# 2025-03-07_main_board.net
KiCad netlist of a schematic drawn in EAGLE
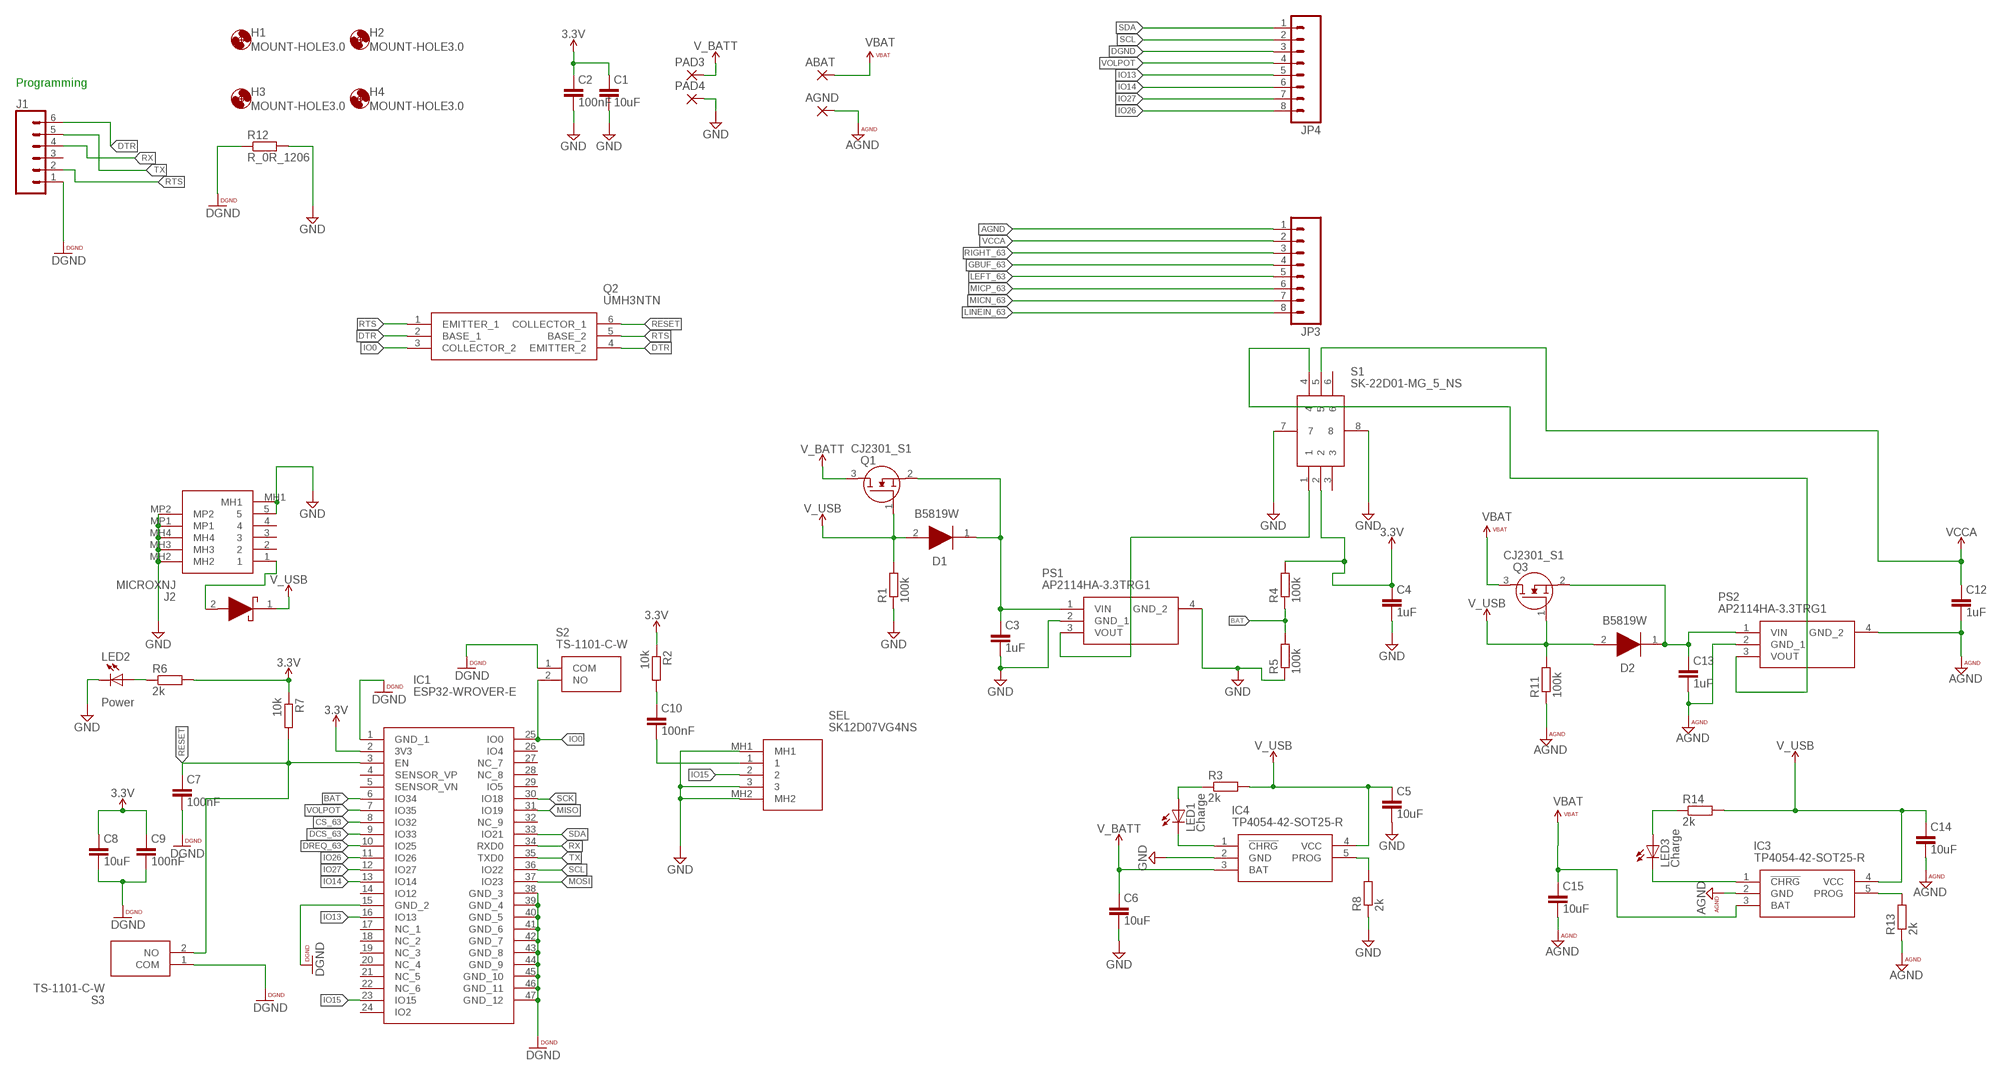
[diagram p0: schematic, sheet 1, part 1 of 2]
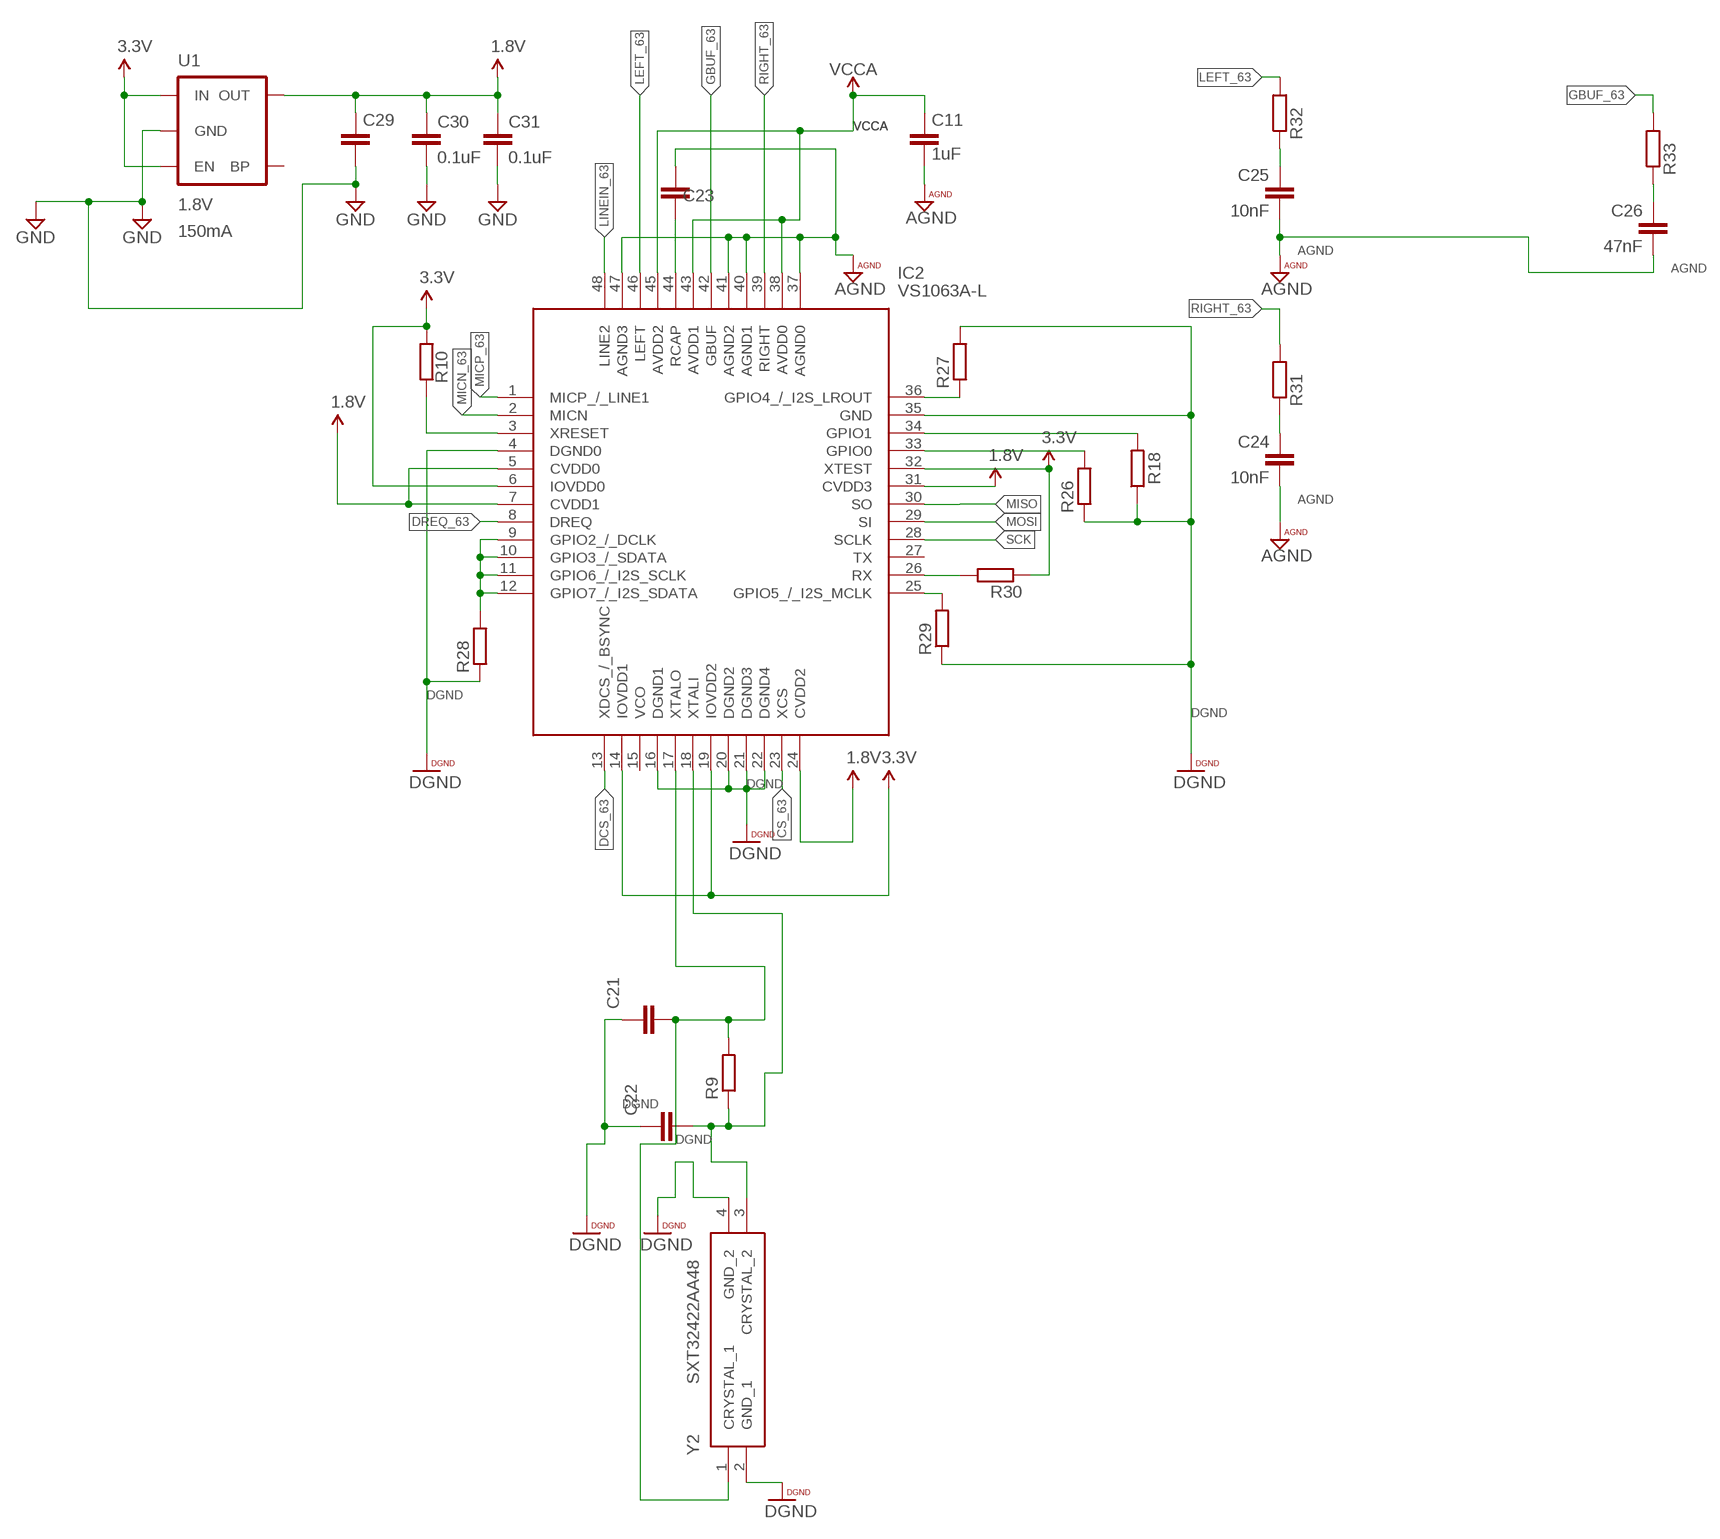
[diagram p1: schematic, sheet 1, part 2 of 2]

(export (version "E")
  (design (tool "Eeschema 10.0.6"))
  (components
    (comp (ref "ABAT")
      (value "2,54/0,8")
      (footprint "eagle-import:2,54_0,8")
      (libsource (lib "eagle-import") (part "2,54/0,8"))
    )
    (comp (ref "AGND")
      (value "2,54/0,8")
      (footprint "eagle-import:2,54_0,8")
      (libsource (lib "eagle-import") (part "2,54/0,8"))
    )
    (comp (ref "C1")
      (value "10uF")
      (footprint "eagle-import:C0603")
      (fields (field (name "LCSC_PART") "C96446"))
      (libsource (lib "eagle-import") (part "C__060310UF/25V"))
    )
    (comp (ref "C2")
      (value "100nF")
      (footprint "eagle-import:C0603")
      (fields (field (name "LCSC_PART") "C14663"))
      (libsource (lib "eagle-import") (part "C__0603100NF/50V"))
    )
    (comp (ref "C3")
      (value "1uF")
      (footprint "eagle-import:C0402")
      (fields (field (name "LCSC_PART") "C52923"))
      (libsource (lib "eagle-import") (part "C__04021UF/25V"))
    )
    (comp (ref "C4")
      (value "1uF")
      (footprint "eagle-import:C0402")
      (fields (field (name "LCSC_PART") "C52923"))
      (libsource (lib "eagle-import") (part "C__04021UF/25V"))
    )
    (comp (ref "C5")
      (value "10uF")
      (footprint "eagle-import:C0603")
      (fields (field (name "LCSC_PART") "C96446"))
      (libsource (lib "eagle-import") (part "C__060310UF/25V"))
    )
    (comp (ref "C6")
      (value "10uF")
      (footprint "eagle-import:C0603")
      (fields (field (name "LCSC_PART") "C96446"))
      (libsource (lib "eagle-import") (part "C__060310UF/25V"))
    )
    (comp (ref "C7")
      (value "100nF")
      (footprint "eagle-import:C0603")
      (fields (field (name "LCSC_PART") "C14663"))
      (libsource (lib "eagle-import") (part "C__0603100NF/50V"))
    )
    (comp (ref "C8")
      (value "10uF")
      (footprint "eagle-import:C0603")
      (fields (field (name "LCSC_PART") "C96446"))
      (libsource (lib "eagle-import") (part "C__060310UF/25V"))
    )
    (comp (ref "C9")
      (value "100nF")
      (footprint "eagle-import:C0603")
      (fields (field (name "LCSC_PART") "C14663"))
      (libsource (lib "eagle-import") (part "C__0603100NF/50V"))
    )
    (comp (ref "C10")
      (value "100nF")
      (footprint "eagle-import:C0603")
      (fields (field (name "LCSC_PART") "C14663"))
      (libsource (lib "eagle-import") (part "C__0603100NF/50V"))
    )
    (comp (ref "C11")
      (value "1uF")
      (footprint "eagle-import:C0402")
      (fields (field (name "LCSC_PART") "C52923"))
      (libsource (lib "eagle-import") (part "C__04021UF/25V"))
    )
    (comp (ref "C12")
      (value "1uF")
      (footprint "eagle-import:C0402")
      (fields (field (name "LCSC_PART") "C52923"))
      (libsource (lib "eagle-import") (part "C__04021UF/25V"))
    )
    (comp (ref "C13")
      (value "1uF")
      (footprint "eagle-import:C0402")
      (fields (field (name "LCSC_PART") "C52923"))
      (libsource (lib "eagle-import") (part "C__04021UF/25V"))
    )
    (comp (ref "C14")
      (value "10uF")
      (footprint "eagle-import:C0603")
      (fields (field (name "LCSC_PART") "C96446"))
      (libsource (lib "eagle-import") (part "C__060310UF/25V"))
    )
    (comp (ref "C15")
      (value "10uF")
      (footprint "eagle-import:C0603")
      (fields (field (name "LCSC_PART") "C96446"))
      (libsource (lib "eagle-import") (part "C__060310UF/25V"))
    )
    (comp (ref "C21")
      (value "22pF")
      (footprint "eagle-import:C0603")
      (fields (field (name "LCSC_PART") "C38523"))
      (libsource (lib "eagle-import") (part "C__060312PF/50V"))
    )
    (comp (ref "C22")
      (value "22pF")
      (footprint "eagle-import:C0603")
      (fields (field (name "LCSC_PART") "C38523"))
      (libsource (lib "eagle-import") (part "C__060312PF/50V"))
    )
    (comp (ref "C23")
      (value "1.0uF")
      (footprint "eagle-import:C0402")
      (fields (field (name "LCSC_PART") "C52923"))
      (libsource (lib "eagle-import") (part "C__04021UF/25V"))
    )
    (comp (ref "C24")
      (value "10nF")
      (footprint "eagle-import:0603-CAP")
      (libsource (lib "eagle-import") (part "10NF/10000PF-50V-10%(0603)"))
    )
    (comp (ref "C25")
      (value "10nF")
      (footprint "eagle-import:0603-CAP")
      (libsource (lib "eagle-import") (part "10NF/10000PF-50V-10%(0603)"))
    )
    (comp (ref "C26")
      (value "47nF")
      (footprint "eagle-import:0603-CAP")
      (libsource (lib "eagle-import") (part "47NF(0.047UF/47000PF)-25V-5%(0603)SMD"))
    )
    (comp (ref "C29")
      (value "10uF")
      (footprint "eagle-import:C0603")
      (fields (field (name "LCSC_PART") "C96446"))
      (libsource (lib "eagle-import") (part "C__060310UF/25V"))
    )
    (comp (ref "C30")
      (value "0.1uF")
      (footprint "eagle-import:0603-CAP")
      (libsource (lib "eagle-import") (part "0.1UF-25V(+80/-20%)(0603)"))
    )
    (comp (ref "C31")
      (value "0.1uF")
      (footprint "eagle-import:0603-CAP")
      (libsource (lib "eagle-import") (part "0.1UF-25V(+80/-20%)(0603)"))
    )
    (comp (ref "D1")
      (value "B5819W")
      (footprint "eagle-import:SOD3716X125N")
      (libsource (lib "eagle-import") (part "B5819W"))
    )
    (comp (ref "D2")
      (value "B5819W")
      (footprint "eagle-import:SOD3716X125N")
      (libsource (lib "eagle-import") (part "B5819W"))
    )
    (comp (ref "D5")
      (value "BAT760-7")
      (footprint "eagle-import:SOD2513X120N")
      (fields (field (name "MOUSER_PART_NUMBER") "621-BAT760-7"))
      (libsource (lib "eagle-import") (part "BAT760-7"))
    )
    (comp (ref "H1")
      (value "MOUNT-HOLE3.0")
      (footprint "eagle-import:3,0")
      (libsource (lib "eagle-import") (part "MOUNT-HOLE3.0"))
    )
    (comp (ref "H2")
      (value "MOUNT-HOLE3.0")
      (footprint "eagle-import:3,0")
      (libsource (lib "eagle-import") (part "MOUNT-HOLE3.0"))
    )
    (comp (ref "H3")
      (value "MOUNT-HOLE3.0")
      (footprint "eagle-import:3,0")
      (libsource (lib "eagle-import") (part "MOUNT-HOLE3.0"))
    )
    (comp (ref "H4")
      (value "MOUNT-HOLE3.0")
      (footprint "eagle-import:3,0")
      (libsource (lib "eagle-import") (part "MOUNT-HOLE3.0"))
    )
    (comp (ref "IC1")
      (value "ESP32-WROVER-E")
      (footprint "eagle-import:ESP32WROVERE")
      (libsource (lib "eagle-import") (part "ESP32-WROVER-E"))
    )
    (comp (ref "IC2")
      (value "VS1063A-L")
      (footprint "eagle-import:QFP50P900X900X160-48N")
      (libsource (lib "eagle-import") (part "VS1063A-L"))
    )
    (comp (ref "IC3")
      (value "TP4054-42-SOT25-R")
      (footprint "eagle-import:SOT95P280X100-5N")
      (libsource (lib "eagle-import") (part "TP4054-42-SOT25-R"))
    )
    (comp (ref "IC4")
      (value "TP4054-42-SOT25-R")
      (footprint "eagle-import:SOT95P280X100-5N")
      (libsource (lib "eagle-import") (part "TP4054-42-SOT25-R"))
    )
    (comp (ref "J1")
      (value "CONN_06NO_SILK_FEMALE_PTH")
      (footprint "eagle-import:1X06_NO_SILK")
      (libsource (lib "eagle-import") (part "CONN_06NO_SILK_FEMALE_PTH"))
    )
    (comp (ref "J2")
      (value "MICROXNJ")
      (footprint "eagle-import:MICROXNJ")
      (libsource (lib "eagle-import") (part "MICROXNJ"))
    )
    (comp (ref "JP3")
      (value "M08")
      (footprint "eagle-import:1X08_ROUND")
      (libsource (lib "eagle-import") (part "M08"))
    )
    (comp (ref "JP4")
      (value "M08")
      (footprint "eagle-import:1X08_ROUND")
      (libsource (lib "eagle-import") (part "M08"))
    )
    (comp (ref "LED1")
      (value "Charge")
      (footprint "eagle-import:CHIP-LED0603")
      (libsource (lib "eagle-import") (part "LEDCHIP-LED0603"))
    )
    (comp (ref "LED2")
      (value "Power")
      (footprint "eagle-import:CHIP-LED0603")
      (libsource (lib "eagle-import") (part "LEDCHIP-LED0603"))
    )
    (comp (ref "LED3")
      (value "Charge")
      (footprint "eagle-import:CHIP-LED0603")
      (libsource (lib "eagle-import") (part "LEDCHIP-LED0603"))
    )
    (comp (ref "PAD3")
      (value "2,54/0,8")
      (footprint "eagle-import:2,54_0,8")
      (libsource (lib "eagle-import") (part "2,54/0,8"))
    )
    (comp (ref "PAD4")
      (value "2,54/0,8")
      (footprint "eagle-import:2,54_0,8")
      (libsource (lib "eagle-import") (part "2,54/0,8"))
    )
    (comp (ref "PS1")
      (value "AP2114HA-3.3TRG1")
      (footprint "eagle-import:SOT230P700X180-4N")
      (fields (field (name "MOUSER_PART_NUMBER") "621-AP2114HA-3.3TRG1"))
      (libsource (lib "eagle-import") (part "AP2114HA-3.3TRG1"))
    )
    (comp (ref "PS2")
      (value "AP2114HA-3.3TRG1")
      (footprint "eagle-import:SOT230P700X180-4N")
      (fields (field (name "MOUSER_PART_NUMBER") "621-AP2114HA-3.3TRG1"))
      (libsource (lib "eagle-import") (part "AP2114HA-3.3TRG1"))
    )
    (comp (ref "Q1")
      (value "CJ2301_S1")
      (footprint "eagle-import:SOT95P240X115-3N")
      (fields (field (name "MANUFACTURER_PART_NUMBER") "CJ2301 S1"))
      (libsource (lib "eagle-import") (part "CJ2301_S1"))
    )
    (comp (ref "Q2")
      (value "UMH3NTN")
      (footprint "eagle-import:UMH3NTN")
      (fields (field (name "MOUSER_PART_NUMBER") "755-UMH3NTN"))
      (libsource (lib "eagle-import") (part "UMH3NTN"))
    )
    (comp (ref "Q3")
      (value "CJ2301_S1")
      (footprint "eagle-import:SOT95P240X115-3N")
      (fields (field (name "MANUFACTURER_PART_NUMBER") "CJ2301 S1"))
      (libsource (lib "eagle-import") (part "CJ2301_S1"))
    )
    (comp (ref "R1")
      (value "100k")
      (footprint "eagle-import:R0603")
      (fields (field (name "LCSC_PART") "C25803"))
      (libsource (lib "eagle-import") (part "R__0603100K"))
    )
    (comp (ref "R2")
      (value "10k")
      (footprint "eagle-import:R0603")
      (fields (field (name "LCSC_PART") "C25804"))
      (libsource (lib "eagle-import") (part "R__060310K"))
    )
    (comp (ref "R3")
      (value "2k")
      (footprint "eagle-import:R0603")
      (fields (field (name "LCSC_PART") "C22975"))
      (libsource (lib "eagle-import") (part "R__06032K"))
    )
    (comp (ref "R4")
      (value "100k")
      (footprint "eagle-import:R0603")
      (fields (field (name "LCSC_PART") "C25803"))
      (libsource (lib "eagle-import") (part "R__0603100K"))
    )
    (comp (ref "R5")
      (value "100k")
      (footprint "eagle-import:R0603")
      (fields (field (name "LCSC_PART") "C25803"))
      (libsource (lib "eagle-import") (part "R__0603100K"))
    )
    (comp (ref "R6")
      (value "2k")
      (footprint "eagle-import:R0603")
      (fields (field (name "LCSC_PART") "C22975"))
      (libsource (lib "eagle-import") (part "R__06032K"))
    )
    (comp (ref "R7")
      (value "10k")
      (footprint "eagle-import:R0603")
      (fields (field (name "LCSC_PART") "C25804"))
      (libsource (lib "eagle-import") (part "R__060310K"))
    )
    (comp (ref "R8")
      (value "2k")
      (footprint "eagle-import:R0603")
      (fields (field (name "LCSC_PART") "C22975"))
      (libsource (lib "eagle-import") (part "R__06032K"))
    )
    (comp (ref "R9")
      (value "1M")
      (footprint "eagle-import:R0603")
      (fields (field (name "LCSC_PART") "C22935"))
      (libsource (lib "eagle-import") (part "R__06031M"))
    )
    (comp (ref "R10")
      (value "100k")
      (footprint "eagle-import:R0603")
      (fields (field (name "LCSC_PART") "C25803"))
      (libsource (lib "eagle-import") (part "R__0603100K"))
    )
    (comp (ref "R11")
      (value "100k")
      (footprint "eagle-import:R0603")
      (fields (field (name "LCSC_PART") "C25803"))
      (libsource (lib "eagle-import") (part "R__0603100K"))
    )
    (comp (ref "R12")
      (value "R_0R_1206")
      (footprint "eagle-import:R1206")
      (fields (field (name "LCSC_PART") "C17888"))
      (libsource (lib "eagle-import") (part "R__12060R"))
    )
    (comp (ref "R13")
      (value "2k")
      (footprint "eagle-import:R0603")
      (fields (field (name "LCSC_PART") "C22975"))
      (libsource (lib "eagle-import") (part "R__06032K"))
    )
    (comp (ref "R14")
      (value "2k")
      (footprint "eagle-import:R0603")
      (fields (field (name "LCSC_PART") "C22975"))
      (libsource (lib "eagle-import") (part "R__06032K"))
    )
    (comp (ref "R18")
      (value "100k")
      (footprint "eagle-import:R0603")
      (fields (field (name "LCSC_PART") "C25803"))
      (libsource (lib "eagle-import") (part "R__0603100K"))
    )
    (comp (ref "R26")
      (value "100k")
      (footprint "eagle-import:R0603")
      (fields (field (name "LCSC_PART") "C25803"))
      (libsource (lib "eagle-import") (part "R__0603100K"))
    )
    (comp (ref "R27")
      (value "100k")
      (footprint "eagle-import:R0603")
      (fields (field (name "LCSC_PART") "C25803"))
      (libsource (lib "eagle-import") (part "R__0603100K"))
    )
    (comp (ref "R28")
      (value "100k")
      (footprint "eagle-import:R0603")
      (fields (field (name "LCSC_PART") "C25803"))
      (libsource (lib "eagle-import") (part "R__0603100K"))
    )
    (comp (ref "R29")
      (value "100k")
      (footprint "eagle-import:R0603")
      (fields (field (name "LCSC_PART") "C25803"))
      (libsource (lib "eagle-import") (part "R__0603100K"))
    )
    (comp (ref "R30")
      (value "100k")
      (footprint "eagle-import:R0603")
      (fields (field (name "LCSC_PART") "C25803"))
      (libsource (lib "eagle-import") (part "R__0603100K"))
    )
    (comp (ref "R31")
      (value "20")
      (footprint "eagle-import:R0603")
      (fields (field (name "LCSC_PART") "C22950"))
      (libsource (lib "eagle-import") (part "R__060320R"))
    )
    (comp (ref "R32")
      (value "20")
      (footprint "eagle-import:R0603")
      (fields (field (name "LCSC_PART") "C22950"))
      (libsource (lib "eagle-import") (part "R__060320R"))
    )
    (comp (ref "R33")
      (value "10")
      (footprint "eagle-import:R0603")
      (fields (field (name "LCSC_PART") "C22859"))
      (libsource (lib "eagle-import") (part "R__060310R"))
    )
    (comp (ref "S1")
      (value "SK-22D01-MG_5_NS")
      (footprint "eagle-import:SK22D01MG5NS")
      (fields
        (field (name "ARROW_PART_NUMBER") "SK-22D01-MG 5 NS")
        (field (name "MOUSER_PART_NUMBER") "611-SK-22D01-MG5NS")
      )
      (libsource (lib "eagle-import") (part "SK-22D01-MG_5_NS"))
    )
    (comp (ref "S2")
      (value "TS-1101-C-W")
      (footprint "eagle-import:TS1101CW")
      (libsource (lib "eagle-import") (part "TS-1101-C-W"))
    )
    (comp (ref "S3")
      (value "TS-1101-C-W")
      (footprint "eagle-import:TS1101CW")
      (libsource (lib "eagle-import") (part "TS-1101-C-W"))
    )
    (comp (ref "SEL")
      (value "SK12D07VG4NS")
      (footprint "eagle-import:SK12D07VG4NS")
      (fields (field (name "MOUSER_PART_NUMBER") "611-SK12D07VG4NS"))
      (libsource (lib "eagle-import") (part "SK12D07VG4NS"))
    )
    (comp (ref "U1")
      (value "1.8V")
      (footprint "eagle-import:SC70")
      (libsource (lib "eagle-import") (part "V_REG_SP62141.8V"))
    )
    (comp (ref "Y2")
      (value "SXT32422AA48")
      (footprint "eagle-import:SXT32422AA48")
      (libsource (lib "eagle-import") (part "SXT32422AA48"))
    )
  )
  (nets
    (net (code "1") (name "1.8V") (class "Default")
      (node (ref "C29") (pin "1") (pinfunction "1_1") (pintype "passive"))
      (node (ref "C30") (pin "1") (pinfunction "1_1") (pintype "passive"))
      (node (ref "C31") (pin "1") (pinfunction "1_1") (pintype "passive"))
      (node (ref "IC2") (pin "24") (pinfunction "CVDD2_24") (pintype "bidirectional"))
      (node (ref "IC2") (pin "31") (pinfunction "CVDD3_31") (pintype "bidirectional"))
      (node (ref "IC2") (pin "5") (pinfunction "CVDD0_5") (pintype "bidirectional"))
      (node (ref "IC2") (pin "7") (pinfunction "CVDD1_7") (pintype "bidirectional"))
      (node (ref "U1") (pin "5") (pinfunction "OUT_5") (pintype "passive"))
    )
    (net (code "2") (name "3.3V") (class "Default")
      (node (ref "C1") (pin "1") (pinfunction "1_1") (pintype "passive"))
      (node (ref "C2") (pin "1") (pinfunction "1_1") (pintype "passive"))
      (node (ref "C4") (pin "1") (pinfunction "1_1") (pintype "passive"))
      (node (ref "C8") (pin "1") (pinfunction "1_1") (pintype "passive"))
      (node (ref "C9") (pin "1") (pinfunction "1_1") (pintype "passive"))
      (node (ref "IC1") (pin "2") (pinfunction "3V3_2") (pintype "bidirectional"))
      (node (ref "IC2") (pin "14") (pinfunction "IOVDD1_14") (pintype "bidirectional"))
      (node (ref "IC2") (pin "19") (pinfunction "IOVDD2_19") (pintype "bidirectional"))
      (node (ref "IC2") (pin "32") (pinfunction "XTEST_32") (pintype "bidirectional"))
      (node (ref "IC2") (pin "6") (pinfunction "IOVDD0_6") (pintype "bidirectional"))
      (node (ref "R10") (pin "2") (pinfunction "2_2") (pintype "passive"))
      (node (ref "R2") (pin "1") (pinfunction "1_1") (pintype "passive"))
      (node (ref "R30") (pin "1") (pinfunction "1_1") (pintype "passive"))
      (node (ref "R4") (pin "2") (pinfunction "2_2") (pintype "passive"))
      (node (ref "R6") (pin "2") (pinfunction "2_2") (pintype "passive"))
      (node (ref "R7") (pin "1") (pinfunction "1_1") (pintype "passive"))
      (node (ref "S1") (pin "2") (pinfunction "2_2") (pintype "bidirectional"))
      (node (ref "U1") (pin "1") (pinfunction "IN_1") (pintype "input"))
      (node (ref "U1") (pin "3") (pinfunction "EN_3") (pintype "input"))
    )
    (net (code "3") (name "AGND") (class "Default")
      (node (ref "AGND") (pin "1") (pinfunction "P_1") (pintype "passive"))
      (node (ref "C11") (pin "2") (pinfunction "2_2") (pintype "passive"))
      (node (ref "C12") (pin "2") (pinfunction "2_2") (pintype "passive"))
      (node (ref "C13") (pin "2") (pinfunction "2_2") (pintype "passive"))
      (node (ref "C14") (pin "2") (pinfunction "2_2") (pintype "passive"))
      (node (ref "C15") (pin "2") (pinfunction "2_2") (pintype "passive"))
      (node (ref "C23") (pin "2") (pinfunction "2_2") (pintype "passive"))
      (node (ref "C24") (pin "2") (pinfunction "2_2") (pintype "passive"))
      (node (ref "C25") (pin "2") (pinfunction "2_2") (pintype "passive"))
      (node (ref "C26") (pin "2") (pinfunction "2_2") (pintype "passive"))
      (node (ref "IC2") (pin "37") (pinfunction "AGND0_37") (pintype "bidirectional"))
      (node (ref "IC2") (pin "40") (pinfunction "AGND1_40") (pintype "bidirectional"))
      (node (ref "IC2") (pin "41") (pinfunction "AGND2_41") (pintype "bidirectional"))
      (node (ref "IC2") (pin "47") (pinfunction "AGND3_47") (pintype "bidirectional"))
      (node (ref "IC3") (pin "2") (pinfunction "GND_2") (pintype "bidirectional"))
      (node (ref "JP3") (pin "1") (pinfunction "1_1") (pintype "passive"))
      (node (ref "PS2") (pin "2") (pinfunction "GND_1_2") (pintype "power_in"))
      (node (ref "PS2") (pin "4") (pinfunction "GND_2_4") (pintype "power_in"))
      (node (ref "R11") (pin "1") (pinfunction "1_1") (pintype "passive"))
      (node (ref "R13") (pin "1") (pinfunction "1_1") (pintype "passive"))
    )
    (net (code "4") (name "BAT") (class "Default")
      (node (ref "IC1") (pin "6") (pinfunction "IO34_6") (pintype "bidirectional"))
      (node (ref "R4") (pin "1") (pinfunction "1_1") (pintype "passive"))
      (node (ref "R5") (pin "2") (pinfunction "2_2") (pintype "passive"))
    )
    (net (code "5") (name "CS_63") (class "Default")
      (node (ref "IC1") (pin "8") (pinfunction "IO32_8") (pintype "bidirectional"))
      (node (ref "IC2") (pin "23") (pinfunction "XCS_23") (pintype "bidirectional"))
    )
    (net (code "6") (name "DCS_63") (class "Default")
      (node (ref "IC1") (pin "9") (pinfunction "IO33_9") (pintype "bidirectional"))
      (node (ref "IC2") (pin "13") (pinfunction "XDCS_/_BSYNC_13") (pintype "bidirectional"))
    )
    (net (code "7") (name "DGND") (class "Default")
      (node (ref "C21") (pin "1") (pinfunction "1_1") (pintype "passive"))
      (node (ref "C22") (pin "1") (pinfunction "1_1") (pintype "passive"))
      (node (ref "C7") (pin "2") (pinfunction "2_2") (pintype "passive"))
      (node (ref "C8") (pin "2") (pinfunction "2_2") (pintype "passive"))
      (node (ref "C9") (pin "2") (pinfunction "2_2") (pintype "passive"))
      (node (ref "IC1") (pin "1") (pinfunction "GND_1_1") (pintype "bidirectional"))
      (node (ref "IC1") (pin "15") (pinfunction "GND_2_15") (pintype "bidirectional"))
      (node (ref "IC1") (pin "38") (pinfunction "GND_3_38") (pintype "bidirectional"))
      (node (ref "IC1") (pin "39") (pinfunction "GND_4_39") (pintype "bidirectional"))
      (node (ref "IC1") (pin "40") (pinfunction "GND_5_40") (pintype "bidirectional"))
      (node (ref "IC1") (pin "41") (pinfunction "GND_6_41") (pintype "bidirectional"))
      (node (ref "IC1") (pin "42") (pinfunction "GND_7_42") (pintype "bidirectional"))
      (node (ref "IC1") (pin "43") (pinfunction "GND_8_43") (pintype "bidirectional"))
      (node (ref "IC1") (pin "44") (pinfunction "GND_9_44") (pintype "bidirectional"))
      (node (ref "IC1") (pin "45") (pinfunction "GND_10_45") (pintype "bidirectional"))
      (node (ref "IC1") (pin "46") (pinfunction "GND_11_46") (pintype "bidirectional"))
      (node (ref "IC1") (pin "47") (pinfunction "GND_12_47") (pintype "bidirectional"))
      (node (ref "IC2") (pin "16") (pinfunction "DGND1_16") (pintype "bidirectional"))
      (node (ref "IC2") (pin "20") (pinfunction "DGND2_20") (pintype "bidirectional"))
      (node (ref "IC2") (pin "21") (pinfunction "DGND3_21") (pintype "bidirectional"))
      (node (ref "IC2") (pin "22") (pinfunction "DGND4_22") (pintype "bidirectional"))
      (node (ref "IC2") (pin "35") (pinfunction "GND_35") (pintype "bidirectional"))
      (node (ref "IC2") (pin "4") (pinfunction "DGND0_4") (pintype "bidirectional"))
      (node (ref "J1") (pin "1") (pinfunction "1_1") (pintype "passive"))
      (node (ref "JP4") (pin "3") (pinfunction "3_3") (pintype "passive"))
      (node (ref "R12") (pin "1") (pinfunction "1_1") (pintype "passive"))
      (node (ref "R18") (pin "1") (pinfunction "1_1") (pintype "passive"))
      (node (ref "R26") (pin "1") (pinfunction "1_1") (pintype "passive"))
      (node (ref "R27") (pin "2") (pinfunction "2_2") (pintype "passive"))
      (node (ref "R28") (pin "1") (pinfunction "1_1") (pintype "passive"))
      (node (ref "R29") (pin "1") (pinfunction "1_1") (pintype "passive"))
      (node (ref "S2") (pin "1") (pinfunction "COM_1") (pintype "bidirectional"))
      (node (ref "S3") (pin "1") (pinfunction "COM_1") (pintype "bidirectional"))
      (node (ref "Y2") (pin "2") (pinfunction "GND_1_2") (pintype "bidirectional"))
      (node (ref "Y2") (pin "4") (pinfunction "GND_2_4") (pintype "bidirectional"))
    )
    (net (code "8") (name "DREQ_63") (class "Default")
      (node (ref "IC1") (pin "10") (pinfunction "IO25_10") (pintype "bidirectional"))
      (node (ref "IC2") (pin "8") (pinfunction "DREQ_8") (pintype "bidirectional"))
    )
    (net (code "9") (name "DTR") (class "Default")
      (node (ref "J1") (pin "6") (pinfunction "6_6") (pintype "passive"))
      (node (ref "Q2") (pin "2") (pinfunction "BASE_1_2") (pintype "bidirectional"))
      (node (ref "Q2") (pin "4") (pinfunction "EMITTER_2_4") (pintype "bidirectional"))
    )
    (net (code "10") (name "GBUF_63") (class "Default")
      (node (ref "IC2") (pin "42") (pinfunction "GBUF_42") (pintype "bidirectional"))
      (node (ref "JP3") (pin "4") (pinfunction "4_4") (pintype "passive"))
      (node (ref "R33") (pin "2") (pinfunction "2_2") (pintype "passive"))
    )
    (net (code "11") (name "GND") (class "Default")
      (node (ref "C1") (pin "2") (pinfunction "2_2") (pintype "passive"))
      (node (ref "C2") (pin "2") (pinfunction "2_2") (pintype "passive"))
      (node (ref "C29") (pin "2") (pinfunction "2_2") (pintype "passive"))
      (node (ref "C3") (pin "2") (pinfunction "2_2") (pintype "passive"))
      (node (ref "C30") (pin "2") (pinfunction "2_2") (pintype "passive"))
      (node (ref "C31") (pin "2") (pinfunction "2_2") (pintype "passive"))
      (node (ref "C4") (pin "2") (pinfunction "2_2") (pintype "passive"))
      (node (ref "C5") (pin "2") (pinfunction "2_2") (pintype "passive"))
      (node (ref "C6") (pin "2") (pinfunction "2_2") (pintype "passive"))
      (node (ref "IC4") (pin "2") (pinfunction "GND_2") (pintype "bidirectional"))
      (node (ref "J2") (pin "5") (pinfunction "5_5") (pintype "bidirectional"))
      (node (ref "J2") (pin "MH1") (pinfunction "MH1_MH1") (pintype "bidirectional"))
      (node (ref "J2") (pin "MH2") (pinfunction "MH2_MH2") (pintype "bidirectional"))
      (node (ref "J2") (pin "MH3") (pinfunction "MH3_MH3") (pintype "bidirectional"))
      (node (ref "J2") (pin "MH4") (pinfunction "MH4_MH4") (pintype "bidirectional"))
      (node (ref "J2") (pin "MP1") (pinfunction "MP1_MP1") (pintype "bidirectional"))
      (node (ref "J2") (pin "MP2") (pinfunction "MP2_MP2") (pintype "bidirectional"))
      (node (ref "LED2") (pin "C") (pinfunction "C_C") (pintype "passive"))
      (node (ref "PAD4") (pin "1") (pinfunction "P_1") (pintype "passive"))
      (node (ref "PS1") (pin "2") (pinfunction "GND_1_2") (pintype "power_in"))
      (node (ref "PS1") (pin "4") (pinfunction "GND_2_4") (pintype "power_in"))
      (node (ref "R1") (pin "1") (pinfunction "1_1") (pintype "passive"))
      (node (ref "R12") (pin "2") (pinfunction "2_2") (pintype "passive"))
      (node (ref "R5") (pin "1") (pinfunction "1_1") (pintype "passive"))
      (node (ref "R8") (pin "1") (pinfunction "1_1") (pintype "passive"))
      (node (ref "S1") (pin "7") (pinfunction "7_7") (pintype "bidirectional"))
      (node (ref "S1") (pin "8") (pinfunction "8_8") (pintype "bidirectional"))
      (node (ref "SEL") (pin "3") (pinfunction "3_3") (pintype "bidirectional"))
      (node (ref "SEL") (pin "MH1") (pinfunction "MH1_MH1") (pintype "bidirectional"))
      (node (ref "SEL") (pin "MH2") (pinfunction "MH2_MH2") (pintype "bidirectional"))
      (node (ref "U1") (pin "2") (pinfunction "GND_2") (pintype "input"))
    )
    (net (code "12") (name "IO0") (class "Default")
      (node (ref "IC1") (pin "25") (pinfunction "IO0_25") (pintype "bidirectional"))
      (node (ref "Q2") (pin "3") (pinfunction "COLLECTOR_2_3") (pintype "bidirectional"))
      (node (ref "S2") (pin "2") (pinfunction "NO_2") (pintype "bidirectional"))
    )
    (net (code "13") (name "IO13") (class "Default")
      (node (ref "IC1") (pin "16") (pinfunction "IO13_16") (pintype "bidirectional"))
      (node (ref "JP4") (pin "5") (pinfunction "5_5") (pintype "passive"))
    )
    (net (code "14") (name "IO14") (class "Default")
      (node (ref "IC1") (pin "13") (pinfunction "IO14_13") (pintype "bidirectional"))
      (node (ref "JP4") (pin "6") (pinfunction "6_6") (pintype "passive"))
    )
    (net (code "15") (name "IO15") (class "Default")
      (node (ref "IC1") (pin "23") (pinfunction "IO15_23") (pintype "bidirectional"))
      (node (ref "SEL") (pin "2") (pinfunction "2_2") (pintype "bidirectional"))
    )
    (net (code "16") (name "IO26") (class "Default")
      (node (ref "IC1") (pin "11") (pinfunction "IO26_11") (pintype "bidirectional"))
      (node (ref "JP4") (pin "8") (pinfunction "8_8") (pintype "passive"))
    )
    (net (code "17") (name "IO27") (class "Default")
      (node (ref "IC1") (pin "12") (pinfunction "IO27_12") (pintype "bidirectional"))
      (node (ref "JP4") (pin "7") (pinfunction "7_7") (pintype "passive"))
    )
    (net (code "18") (name "LEFT_63") (class "Default")
      (node (ref "IC2") (pin "46") (pinfunction "LEFT_46") (pintype "bidirectional"))
      (node (ref "JP3") (pin "5") (pinfunction "5_5") (pintype "passive"))
      (node (ref "R32") (pin "2") (pinfunction "2_2") (pintype "passive"))
    )
    (net (code "19") (name "LINEIN_63") (class "Default")
      (node (ref "IC2") (pin "48") (pinfunction "LINE2_48") (pintype "bidirectional"))
      (node (ref "JP3") (pin "8") (pinfunction "8_8") (pintype "passive"))
    )
    (net (code "20") (name "MICN_63") (class "Default")
      (node (ref "IC2") (pin "2") (pinfunction "MICN_2") (pintype "bidirectional"))
      (node (ref "JP3") (pin "7") (pinfunction "7_7") (pintype "passive"))
    )
    (net (code "21") (name "MICP_63") (class "Default")
      (node (ref "IC2") (pin "1") (pinfunction "MICP_/_LINE1_1") (pintype "bidirectional"))
      (node (ref "JP3") (pin "6") (pinfunction "6_6") (pintype "passive"))
    )
    (net (code "22") (name "MISO") (class "Default")
      (node (ref "IC1") (pin "31") (pinfunction "IO19_31") (pintype "bidirectional"))
      (node (ref "IC2") (pin "30") (pinfunction "SO_30") (pintype "bidirectional"))
    )
    (net (code "23") (name "MOSI") (class "Default")
      (node (ref "IC1") (pin "37") (pinfunction "IO23_37") (pintype "bidirectional"))
      (node (ref "IC2") (pin "29") (pinfunction "SI_29") (pintype "bidirectional"))
    )
    (net (code "24") (name "Net-(C10-Pad1)") (class "Default")
      (node (ref "C10") (pin "1") (pinfunction "1_1") (pintype "passive"))
      (node (ref "R2") (pin "2") (pinfunction "2_2") (pintype "passive"))
    )
    (net (code "25") (name "Net-(C10-Pad2)") (class "Default")
      (node (ref "C10") (pin "2") (pinfunction "2_2") (pintype "passive"))
      (node (ref "SEL") (pin "1") (pinfunction "1_1") (pintype "bidirectional"))
    )
    (net (code "26") (name "Net-(C24-Pad1)") (class "Default")
      (node (ref "C24") (pin "1") (pinfunction "1_1") (pintype "passive"))
      (node (ref "R31") (pin "1") (pinfunction "1_1") (pintype "passive"))
    )
    (net (code "27") (name "Net-(C25-Pad1)") (class "Default")
      (node (ref "C25") (pin "1") (pinfunction "1_1") (pintype "passive"))
      (node (ref "R32") (pin "1") (pinfunction "1_1") (pintype "passive"))
    )
    (net (code "28") (name "Net-(C26-Pad1)") (class "Default")
      (node (ref "C26") (pin "1") (pinfunction "1_1") (pintype "passive"))
      (node (ref "R33") (pin "1") (pinfunction "1_1") (pintype "passive"))
    )
    (net (code "29") (name "Net-(D1-K)") (class "Default")
      (node (ref "C3") (pin "1") (pinfunction "1_1") (pintype "passive"))
      (node (ref "D1") (pin "1") (pinfunction "K_1") (pintype "bidirectional"))
      (node (ref "PS1") (pin "1") (pinfunction "VIN_1") (pintype "input"))
      (node (ref "Q1") (pin "2") (pinfunction "S_2") (pintype "bidirectional"))
    )
    (net (code "30") (name "Net-(D2-K)") (class "Default")
      (node (ref "C13") (pin "1") (pinfunction "1_1") (pintype "passive"))
      (node (ref "D2") (pin "1") (pinfunction "K_1") (pintype "bidirectional"))
      (node (ref "PS2") (pin "1") (pinfunction "VIN_1") (pintype "input"))
      (node (ref "Q3") (pin "2") (pinfunction "S_2") (pintype "bidirectional"))
    )
    (net (code "31") (name "Net-(D5-A)") (class "Default")
      (node (ref "D5") (pin "2") (pinfunction "A_2") (pintype "bidirectional"))
      (node (ref "J2") (pin "1") (pinfunction "1_1") (pintype "bidirectional"))
    )
    (net (code "32") (name "Net-(IC2-GPIO0)") (class "Default")
      (node (ref "IC2") (pin "33") (pinfunction "GPIO0_33") (pintype "bidirectional"))
      (node (ref "R26") (pin "2") (pinfunction "2_2") (pintype "passive"))
    )
    (net (code "33") (name "Net-(IC2-GPIO1)") (class "Default")
      (node (ref "IC2") (pin "34") (pinfunction "GPIO1_34") (pintype "bidirectional"))
      (node (ref "R18") (pin "2") (pinfunction "2_2") (pintype "passive"))
    )
    (net (code "34") (name "Net-(IC2-GPIO2_{slash}_DCLK)") (class "Default")
      (node (ref "IC2") (pin "10") (pinfunction "GPIO3_/_SDATA_10") (pintype "bidirectional"))
      (node (ref "IC2") (pin "11") (pinfunction "GPIO6_/_I2S_SCLK_11") (pintype "bidirectional"))
      (node (ref "IC2") (pin "12") (pinfunction "GPIO7_/_I2S_SDATA_12") (pintype "bidirectional"))
      (node (ref "IC2") (pin "9") (pinfunction "GPIO2_/_DCLK_9") (pintype "bidirectional"))
      (node (ref "R28") (pin "2") (pinfunction "2_2") (pintype "passive"))
    )
    (net (code "35") (name "Net-(IC2-GPIO4_{slash}_I2S_LROUT)") (class "Default")
      (node (ref "IC2") (pin "36") (pinfunction "GPIO4_/_I2S_LROUT_36") (pintype "bidirectional"))
      (node (ref "R27") (pin "1") (pinfunction "1_1") (pintype "passive"))
    )
    (net (code "36") (name "Net-(IC2-GPIO5_{slash}_I2S_MCLK)") (class "Default")
      (node (ref "IC2") (pin "25") (pinfunction "GPIO5_/_I2S_MCLK_25") (pintype "bidirectional"))
      (node (ref "R29") (pin "2") (pinfunction "2_2") (pintype "passive"))
    )
    (net (code "37") (name "Net-(IC2-RCAP)") (class "Default")
      (node (ref "C23") (pin "1") (pinfunction "1_1") (pintype "passive"))
      (node (ref "IC2") (pin "44") (pinfunction "RCAP_44") (pintype "bidirectional"))
    )
    (net (code "38") (name "Net-(IC2-RX)") (class "Default")
      (node (ref "IC2") (pin "26") (pinfunction "RX_26") (pintype "bidirectional"))
      (node (ref "R30") (pin "2") (pinfunction "2_2") (pintype "passive"))
    )
    (net (code "39") (name "Net-(IC2-XRESET)") (class "Default")
      (node (ref "IC2") (pin "3") (pinfunction "XRESET_3") (pintype "bidirectional"))
      (node (ref "R10") (pin "1") (pinfunction "1_1") (pintype "passive"))
    )
    (net (code "40") (name "Net-(IC2-XTALI)") (class "Default")
      (node (ref "C22") (pin "2") (pinfunction "2_2") (pintype "passive"))
      (node (ref "IC2") (pin "18") (pinfunction "XTALI_18") (pintype "bidirectional"))
      (node (ref "R9") (pin "1") (pinfunction "1_1") (pintype "passive"))
      (node (ref "Y2") (pin "3") (pinfunction "CRYSTAL_2_3") (pintype "bidirectional"))
    )
    (net (code "41") (name "Net-(IC2-XTALO)") (class "Default")
      (node (ref "C21") (pin "2") (pinfunction "2_2") (pintype "passive"))
      (node (ref "IC2") (pin "17") (pinfunction "XTALO_17") (pintype "bidirectional"))
      (node (ref "R9") (pin "2") (pinfunction "2_2") (pintype "passive"))
      (node (ref "Y2") (pin "1") (pinfunction "CRYSTAL_1_1") (pintype "bidirectional"))
    )
    (net (code "42") (name "Net-(IC3-PROG)") (class "Default")
      (node (ref "IC3") (pin "5") (pinfunction "PROG_5") (pintype "bidirectional"))
      (node (ref "R13") (pin "2") (pinfunction "2_2") (pintype "passive"))
    )
    (net (code "43") (name "Net-(IC3-~{CHRG})") (class "Default")
      (node (ref "IC3") (pin "1") (pinfunction "~{CHRG}_1") (pintype "bidirectional"))
      (node (ref "LED3") (pin "C") (pinfunction "C_C") (pintype "passive"))
    )
    (net (code "44") (name "Net-(IC4-PROG)") (class "Default")
      (node (ref "IC4") (pin "5") (pinfunction "PROG_5") (pintype "bidirectional"))
      (node (ref "R8") (pin "2") (pinfunction "2_2") (pintype "passive"))
    )
    (net (code "45") (name "Net-(IC4-~{CHRG})") (class "Default")
      (node (ref "IC4") (pin "1") (pinfunction "~{CHRG}_1") (pintype "bidirectional"))
      (node (ref "LED1") (pin "C") (pinfunction "C_C") (pintype "passive"))
    )
    (net (code "46") (name "Net-(LED1-PadA)") (class "Default")
      (node (ref "LED1") (pin "A") (pinfunction "A_A") (pintype "passive"))
      (node (ref "R3") (pin "1") (pinfunction "1_1") (pintype "passive"))
    )
    (net (code "47") (name "Net-(LED2-PadA)") (class "Default")
      (node (ref "LED2") (pin "A") (pinfunction "A_A") (pintype "passive"))
      (node (ref "R6") (pin "1") (pinfunction "1_1") (pintype "passive"))
    )
    (net (code "48") (name "Net-(LED3-PadA)") (class "Default")
      (node (ref "LED3") (pin "A") (pinfunction "A_A") (pintype "passive"))
      (node (ref "R14") (pin "1") (pinfunction "1_1") (pintype "passive"))
    )
    (net (code "49") (name "Net-(PS1-VOUT)") (class "Default")
      (node (ref "PS1") (pin "3") (pinfunction "VOUT_3") (pintype "output"))
      (node (ref "S1") (pin "1") (pinfunction "1_1") (pintype "bidirectional"))
    )
    (net (code "50") (name "Net-(PS2-VOUT)") (class "Default")
      (node (ref "PS2") (pin "3") (pinfunction "VOUT_3") (pintype "output"))
      (node (ref "S1") (pin "4") (pinfunction "4_4") (pintype "bidirectional"))
    )
    (net (code "51") (name "RESET") (class "Default")
      (node (ref "C7") (pin "1") (pinfunction "1_1") (pintype "passive"))
      (node (ref "IC1") (pin "3") (pinfunction "EN_3") (pintype "bidirectional"))
      (node (ref "Q2") (pin "6") (pinfunction "COLLECTOR_1_6") (pintype "bidirectional"))
      (node (ref "R7") (pin "2") (pinfunction "2_2") (pintype "passive"))
      (node (ref "S3") (pin "2") (pinfunction "NO_2") (pintype "bidirectional"))
    )
    (net (code "52") (name "RIGHT_63") (class "Default")
      (node (ref "IC2") (pin "39") (pinfunction "RIGHT_39") (pintype "bidirectional"))
      (node (ref "JP3") (pin "3") (pinfunction "3_3") (pintype "passive"))
      (node (ref "R31") (pin "2") (pinfunction "2_2") (pintype "passive"))
    )
    (net (code "53") (name "RTS") (class "Default")
      (node (ref "J1") (pin "2") (pinfunction "2_2") (pintype "passive"))
      (node (ref "Q2") (pin "1") (pinfunction "EMITTER_1_1") (pintype "bidirectional"))
      (node (ref "Q2") (pin "5") (pinfunction "BASE_2_5") (pintype "bidirectional"))
    )
    (net (code "54") (name "RX") (class "Default")
      (node (ref "IC1") (pin "34") (pinfunction "RXD0_34") (pintype "bidirectional"))
      (node (ref "J1") (pin "4") (pinfunction "4_4") (pintype "passive"))
    )
    (net (code "55") (name "SCK") (class "Default")
      (node (ref "IC1") (pin "30") (pinfunction "IO18_30") (pintype "bidirectional"))
      (node (ref "IC2") (pin "28") (pinfunction "SCLK_28") (pintype "bidirectional"))
    )
    (net (code "56") (name "SCL") (class "Default")
      (node (ref "IC1") (pin "36") (pinfunction "IO22_36") (pintype "bidirectional"))
      (node (ref "JP4") (pin "2") (pinfunction "2_2") (pintype "passive"))
    )
    (net (code "57") (name "SDA") (class "Default")
      (node (ref "IC1") (pin "33") (pinfunction "IO21_33") (pintype "bidirectional"))
      (node (ref "JP4") (pin "1") (pinfunction "1_1") (pintype "passive"))
    )
    (net (code "58") (name "TX") (class "Default")
      (node (ref "IC1") (pin "35") (pinfunction "TXD0_35") (pintype "bidirectional"))
      (node (ref "J1") (pin "5") (pinfunction "5_5") (pintype "passive"))
    )
    (net (code "59") (name "VBAT") (class "Default")
      (node (ref "ABAT") (pin "1") (pinfunction "P_1") (pintype "passive"))
      (node (ref "C15") (pin "1") (pinfunction "1_1") (pintype "passive"))
      (node (ref "IC3") (pin "3") (pinfunction "BAT_3") (pintype "bidirectional"))
      (node (ref "Q3") (pin "3") (pinfunction "D_3") (pintype "bidirectional"))
    )
    (net (code "60") (name "VCCA") (class "Default")
      (node (ref "C11") (pin "1") (pinfunction "1_1") (pintype "passive"))
      (node (ref "C12") (pin "1") (pinfunction "1_1") (pintype "passive"))
      (node (ref "IC2") (pin "38") (pinfunction "AVDD0_38") (pintype "bidirectional"))
      (node (ref "IC2") (pin "43") (pinfunction "AVDD1_43") (pintype "bidirectional"))
      (node (ref "IC2") (pin "45") (pinfunction "AVDD2_45") (pintype "bidirectional"))
      (node (ref "JP3") (pin "2") (pinfunction "2_2") (pintype "passive"))
      (node (ref "S1") (pin "5") (pinfunction "5_5") (pintype "bidirectional"))
    )
    (net (code "61") (name "VOLPOT") (class "Default")
      (node (ref "IC1") (pin "7") (pinfunction "IO35_7") (pintype "bidirectional"))
      (node (ref "JP4") (pin "4") (pinfunction "4_4") (pintype "passive"))
    )
    (net (code "62") (name "V_BATT") (class "Default")
      (node (ref "C6") (pin "1") (pinfunction "1_1") (pintype "passive"))
      (node (ref "IC4") (pin "3") (pinfunction "BAT_3") (pintype "bidirectional"))
      (node (ref "PAD3") (pin "1") (pinfunction "P_1") (pintype "passive"))
      (node (ref "Q1") (pin "3") (pinfunction "D_3") (pintype "bidirectional"))
    )
    (net (code "63") (name "V_USB") (class "Default")
      (node (ref "C14") (pin "1") (pinfunction "1_1") (pintype "passive"))
      (node (ref "C5") (pin "1") (pinfunction "1_1") (pintype "passive"))
      (node (ref "D1") (pin "2") (pinfunction "A_2") (pintype "bidirectional"))
      (node (ref "D2") (pin "2") (pinfunction "A_2") (pintype "bidirectional"))
      (node (ref "D5") (pin "1") (pinfunction "K_1") (pintype "bidirectional"))
      (node (ref "IC3") (pin "4") (pinfunction "VCC_4") (pintype "bidirectional"))
      (node (ref "IC4") (pin "4") (pinfunction "VCC_4") (pintype "bidirectional"))
      (node (ref "Q1") (pin "1") (pinfunction "G_1") (pintype "bidirectional"))
      (node (ref "Q3") (pin "1") (pinfunction "G_1") (pintype "bidirectional"))
      (node (ref "R1") (pin "2") (pinfunction "2_2") (pintype "passive"))
      (node (ref "R11") (pin "2") (pinfunction "2_2") (pintype "passive"))
      (node (ref "R14") (pin "2") (pinfunction "2_2") (pintype "passive"))
      (node (ref "R3") (pin "2") (pinfunction "2_2") (pintype "passive"))
    )
    (net (code "64") (name "unconnected-(IC1-IO2-Pad24)") (class "Default")
      (node (ref "IC1") (pin "24") (pinfunction "IO2_24") (pintype "bidirectional"))
    )
    (net (code "65") (name "unconnected-(IC1-IO4-Pad26)") (class "Default")
      (node (ref "IC1") (pin "26") (pinfunction "IO4_26") (pintype "bidirectional"))
    )
    (net (code "66") (name "unconnected-(IC1-IO5-Pad29)") (class "Default")
      (node (ref "IC1") (pin "29") (pinfunction "IO5_29") (pintype "bidirectional"))
    )
    (net (code "67") (name "unconnected-(IC1-IO12-Pad14)") (class "Default")
      (node (ref "IC1") (pin "14") (pinfunction "IO12_14") (pintype "bidirectional"))
    )
    (net (code "68") (name "unconnected-(IC1-NC_1-Pad17)") (class "Default")
      (node (ref "IC1") (pin "17") (pinfunction "NC_1_17") (pintype "bidirectional"))
    )
    (net (code "69") (name "unconnected-(IC1-NC_2-Pad18)") (class "Default")
      (node (ref "IC1") (pin "18") (pinfunction "NC_2_18") (pintype "bidirectional"))
    )
    (net (code "70") (name "unconnected-(IC1-NC_3-Pad19)") (class "Default")
      (node (ref "IC1") (pin "19") (pinfunction "NC_3_19") (pintype "bidirectional"))
    )
    (net (code "71") (name "unconnected-(IC1-NC_4-Pad20)") (class "Default")
      (node (ref "IC1") (pin "20") (pinfunction "NC_4_20") (pintype "bidirectional"))
    )
    (net (code "72") (name "unconnected-(IC1-NC_5-Pad21)") (class "Default")
      (node (ref "IC1") (pin "21") (pinfunction "NC_5_21") (pintype "bidirectional"))
    )
    (net (code "73") (name "unconnected-(IC1-NC_6-Pad22)") (class "Default")
      (node (ref "IC1") (pin "22") (pinfunction "NC_6_22") (pintype "bidirectional"))
    )
    (net (code "74") (name "unconnected-(IC1-NC_7-Pad27)") (class "Default")
      (node (ref "IC1") (pin "27") (pinfunction "NC_7_27") (pintype "bidirectional"))
    )
    (net (code "75") (name "unconnected-(IC1-NC_8-Pad28)") (class "Default")
      (node (ref "IC1") (pin "28") (pinfunction "NC_8_28") (pintype "bidirectional"))
    )
    (net (code "76") (name "unconnected-(IC1-NC_9-Pad32)") (class "Default")
      (node (ref "IC1") (pin "32") (pinfunction "NC_9_32") (pintype "bidirectional"))
    )
    (net (code "77") (name "unconnected-(IC1-SENSOR_VN-Pad5)") (class "Default")
      (node (ref "IC1") (pin "5") (pinfunction "SENSOR_VN_5") (pintype "bidirectional"))
    )
    (net (code "78") (name "unconnected-(IC1-SENSOR_VP-Pad4)") (class "Default")
      (node (ref "IC1") (pin "4") (pinfunction "SENSOR_VP_4") (pintype "bidirectional"))
    )
    (net (code "79") (name "unconnected-(IC2-TX-Pad27)") (class "Default")
      (node (ref "IC2") (pin "27") (pinfunction "TX_27") (pintype "bidirectional"))
    )
    (net (code "80") (name "unconnected-(IC2-VCO-Pad15)") (class "Default")
      (node (ref "IC2") (pin "15") (pinfunction "VCO_15") (pintype "bidirectional"))
    )
    (net (code "81") (name "unconnected-(J1-Pad3)") (class "Default")
      (node (ref "J1") (pin "3") (pinfunction "3_3") (pintype "passive"))
    )
    (net (code "82") (name "unconnected-(J2-Pad2)") (class "Default")
      (node (ref "J2") (pin "2") (pinfunction "2_2") (pintype "bidirectional"))
    )
    (net (code "83") (name "unconnected-(J2-Pad3)") (class "Default")
      (node (ref "J2") (pin "3") (pinfunction "3_3") (pintype "bidirectional"))
    )
    (net (code "84") (name "unconnected-(J2-Pad4)") (class "Default")
      (node (ref "J2") (pin "4") (pinfunction "4_4") (pintype "bidirectional"))
    )
    (net (code "85") (name "unconnected-(S1-Pad3)") (class "Default")
      (node (ref "S1") (pin "3") (pinfunction "3_3") (pintype "bidirectional"))
    )
    (net (code "86") (name "unconnected-(S1-Pad6)") (class "Default")
      (node (ref "S1") (pin "6") (pinfunction "6_6") (pintype "bidirectional"))
    )
    (net (code "87") (name "unconnected-(U1-BP-Pad4)") (class "Default")
      (node (ref "U1") (pin "4") (pinfunction "BP_4") (pintype "input"))
    )
  )
)
